# CAN.net
KiCad netlist of a schematic drawn in Altium Designer
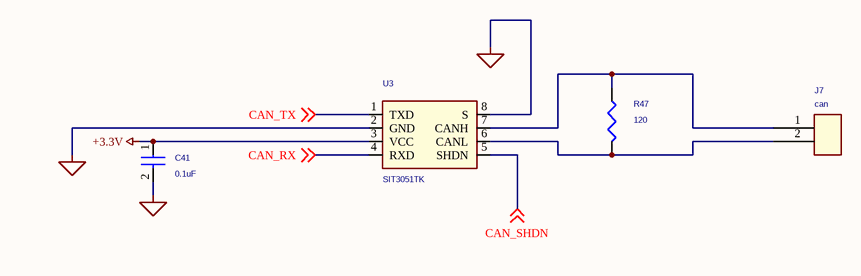
[diagram p0: CAN.SchDoc]

(export (version "E")
  (design (tool "Eeschema 10.0.6"))
  (components
    (comp (ref "C41")
      (value "0.1uF")
      (footprint "C_0402")
      (description "CAP CER 0.1UF 16V X7R 0402")
      (fields (field (name "PART_NUMBER") "CAP-00000053") (field (name "TOLERANCE") "10%"))
      (libsource (lib "*") (part "CAP_Dup1"))
    )
    (comp (ref "J7")
      (value "can")
      (footprint "SOLDER_PAD_2PIN_SMD")
      (description "SOLDER PADS")
      (libsource (lib "MB1419") (part "CON4_3"))
    )
    (comp (ref "R47")
      (value "120")
      (footprint "R_0402")
      (description "RES SMD 120 OHM 1% 1/16W 0402")
      (fields (field (name "PART_NUMBER") "TMP-441") (field (name "TOLERANCE") "1%"))
      (libsource (lib "*") (part "RES"))
    )
    (comp (ref "U3")
      (value "SIT3051TK")
      (footprint "sot23-8p65_280x145l45x30n")
      (description "IC TXRX CAN 3.3V SOT-23")
      (fields (field (name "PART_NUMBER") "TMP-379") (field (name "MANUFACTURER") "Texas Instruments"))
      (libsource (lib "*") (part "TCAN330"))
    )
  )
  (nets
    (net (code "1") (name "+3.3V") (class "Default")
      (node (ref "C41") (pin "1") (pinfunction "1_1") (pintype "passive"))
      (node (ref "U3") (pin "3") (pinfunction "VCC_3") (pintype "passive"))
    )
    (net (code "2") (name "CAN_RX") (class "Default")
      (node (ref "U3") (pin "4") (pinfunction "RXD_4") (pintype "passive"))
    )
    (net (code "3") (name "CAN_SHDN") (class "Default")
      (node (ref "U3") (pin "5") (pinfunction "SHDN_5") (pintype "passive"))
    )
    (net (code "4") (name "CAN_TX") (class "Default")
      (node (ref "U3") (pin "1") (pinfunction "TXD_1") (pintype "passive"))
    )
    (net (code "5") (name "GND_SIGNAL") (class "Default")
      (node (ref "C41") (pin "2") (pinfunction "2_2") (pintype "passive"))
      (node (ref "U3") (pin "2") (pinfunction "GND_2") (pintype "passive"))
      (node (ref "U3") (pin "8") (pinfunction "S_8") (pintype "passive"))
    )
    (net (code "6") (name "Net-(U3-CANH)") (class "Default")
      (node (ref "J7") (pin "1") (pinfunction "1_1") (pintype "passive"))
      (node (ref "R47") (pin "1") (pinfunction "1_1") (pintype "passive"))
      (node (ref "U3") (pin "7") (pinfunction "CANH_7") (pintype "passive"))
    )
    (net (code "7") (name "Net-(U3-CANL)") (class "Default")
      (node (ref "J7") (pin "2") (pinfunction "2_2") (pintype "passive"))
      (node (ref "R47") (pin "2") (pinfunction "2_2") (pintype "passive"))
      (node (ref "U3") (pin "6") (pinfunction "CANL_6") (pintype "passive"))
    )
  )
)
